# circuit_diagram.net
KiCad netlist of a schematic drawn in EAGLE
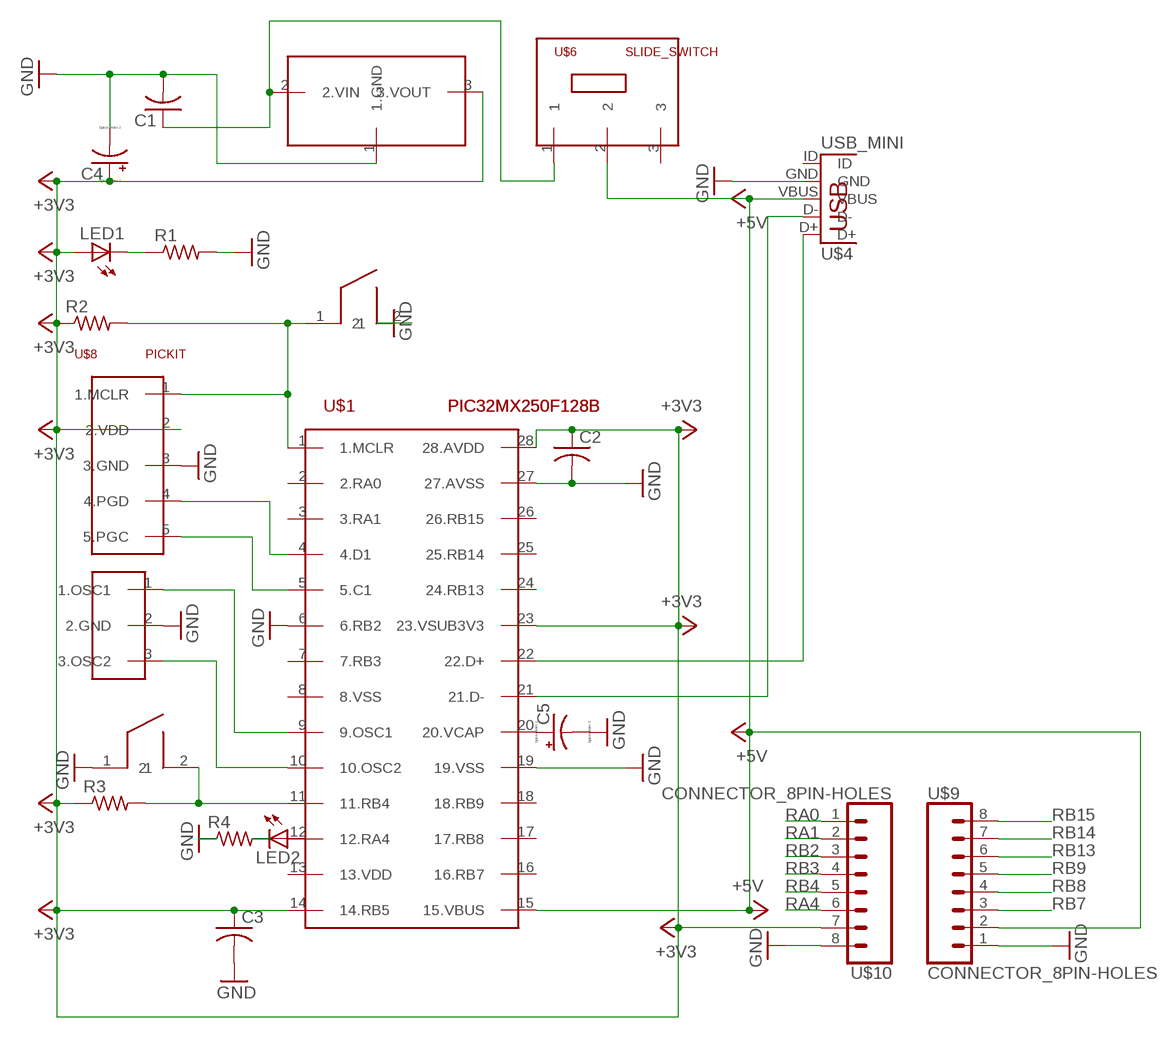
[diagram p0: schematic, sheet 1]

(export (version "E")
  (design (tool "Eeschema 10.0.6"))
  (components
    (comp (ref "C1")
      (value "C-US025-024X044")
      (footprint "eagle-import:C025-024X044")
      (libsource (lib "eagle-import") (part "C-US025-024X044"))
    )
    (comp (ref "C2")
      (value "C-US025-024X044")
      (footprint "eagle-import:C025-024X044")
      (libsource (lib "eagle-import") (part "C-US025-024X044"))
    )
    (comp (ref "C3")
      (value "C-US025-024X044")
      (footprint "eagle-import:C025-024X044")
      (libsource (lib "eagle-import") (part "C-US025-024X044"))
    )
    (comp (ref "C4")
      (value "CPOL-USCT3216")
      (footprint "eagle-import:CT3216")
      (libsource (lib "eagle-import") (part "CPOL-USCT3216"))
    )
    (comp (ref "C5")
      (value "CPOL-USCT3216")
      (footprint "eagle-import:CT3216")
      (libsource (lib "eagle-import") (part "CPOL-USCT3216"))
    )
    (comp (ref "LED1")
      (value "LED3MM")
      (footprint "eagle-import:LED3MM")
      (libsource (lib "eagle-import") (part "LED3MM"))
    )
    (comp (ref "LED2")
      (value "LED3MM")
      (footprint "eagle-import:LED3MM")
      (libsource (lib "eagle-import") (part "LED3MM"))
    )
    (comp (ref "R1")
      (value "R-US_0207/10")
      (footprint "eagle-import:0207_10")
      (libsource (lib "eagle-import") (part "R-US_0207/10"))
    )
    (comp (ref "R2")
      (value "R-US_0207/10")
      (footprint "eagle-import:0207_10")
      (libsource (lib "eagle-import") (part "R-US_0207/10"))
    )
    (comp (ref "R3")
      (value "R-US_0207/10")
      (footprint "eagle-import:0207_10")
      (libsource (lib "eagle-import") (part "R-US_0207/10"))
    )
    (comp (ref "R4")
      (value "R-US_0207/10")
      (footprint "eagle-import:0207_10")
      (libsource (lib "eagle-import") (part "R-US_0207/10"))
    )
    (comp (ref "U$1")
      (value "PIC32MX250F128B")
      (footprint "eagle-import:DIL28-3")
      (libsource (lib "eagle-import") (part "PIC32MX250F128B"))
    )
    (comp (ref "U$2")
      (value "PUSH_BUTTON_SPST-NO")
      (footprint "eagle-import:1X03")
      (libsource (lib "eagle-import") (part "PUSH_BUTTON_SPST-NO"))
    )
    (comp (ref "U$3")
      (value "PUSH_BUTTON_SPST-NO")
      (footprint "eagle-import:1X03")
      (libsource (lib "eagle-import") (part "PUSH_BUTTON_SPST-NO"))
    )
    (comp (ref "U$4")
      (value "USB_MINI")
      (footprint "eagle-import:USB-MB-H")
      (libsource (lib "eagle-import") (part "USB_MINI"))
    )
    (comp (ref "U$5")
      (value "MCP1072")
      (footprint "eagle-import:TO92")
      (libsource (lib "eagle-import") (part "MCP1072"))
    )
    (comp (ref "U$6")
      (value "SLIDE_SWITCH")
      (footprint "eagle-import:SLIDE_SW")
      (libsource (lib "eagle-import") (part "SLIDE_SWITCH"))
    )
    (comp (ref "U$7")
      (value "OSC")
      (footprint "eagle-import:1X03")
      (libsource (lib "eagle-import") (part "OSC"))
    )
    (comp (ref "U$8")
      (value "PICKIT")
      (footprint "eagle-import:1X05")
      (libsource (lib "eagle-import") (part "PICKIT"))
    )
    (comp (ref "U$9")
      (value "CONNECTOR_8PIN-HOLES")
      (footprint "eagle-import:1X08")
      (libsource (lib "eagle-import") (part "CONNECTOR_8PIN-HOLES"))
    )
    (comp (ref "U$10")
      (value "CONNECTOR_8PIN-HOLES")
      (footprint "eagle-import:1X08")
      (libsource (lib "eagle-import") (part "CONNECTOR_8PIN-HOLES"))
    )
  )
  (nets
    (net (code "1") (name "+3V3") (class "Default")
      (node (ref "C2") (pin "1") (pinfunction "1_1") (pintype "passive"))
      (node (ref "C3") (pin "1") (pinfunction "1_1") (pintype "passive"))
      (node (ref "C4") (pin "-") (pinfunction "+_-") (pintype "passive"))
      (node (ref "LED1") (pin "A") (pinfunction "A_A") (pintype "passive"))
      (node (ref "R2") (pin "1") (pinfunction "1_1") (pintype "passive"))
      (node (ref "R3") (pin "1") (pinfunction "1_1") (pintype "passive"))
      (node (ref "U$1") (pin "14") (pinfunction "14.RB5_14") (pintype "bidirectional"))
      (node (ref "U$1") (pin "23") (pinfunction "23.VSUB3V3_23") (pintype "bidirectional"))
      (node (ref "U$1") (pin "28") (pinfunction "28.AVDD_28") (pintype "bidirectional"))
      (node (ref "U$10") (pin "7") (pinfunction "7_7") (pintype "passive"))
      (node (ref "U$5") (pin "3") (pinfunction "3.VOUT_3") (pintype "bidirectional"))
      (node (ref "U$8") (pin "2") (pinfunction "2.VDD_2") (pintype "bidirectional"))
    )
    (net (code "2") (name "+5V") (class "Default")
      (node (ref "U$1") (pin "15") (pinfunction "15.VBUS_15") (pintype "bidirectional"))
      (node (ref "U$4") (pin "VBUS") (pinfunction "VBUS_VBUS") (pintype "bidirectional"))
      (node (ref "U$6") (pin "2") (pinfunction "2_2") (pintype "bidirectional"))
      (node (ref "U$9") (pin "2") (pinfunction "2_2") (pintype "passive"))
    )
    (net (code "3") (name "/RA0") (class "Default")
      (node (ref "U$10") (pin "1") (pinfunction "1_1") (pintype "passive"))
    )
    (net (code "4") (name "/RA1") (class "Default")
      (node (ref "U$10") (pin "2") (pinfunction "2_2") (pintype "passive"))
    )
    (net (code "5") (name "/RA4") (class "Default")
      (node (ref "U$10") (pin "6") (pinfunction "6_6") (pintype "passive"))
    )
    (net (code "6") (name "/RB2") (class "Default")
      (node (ref "U$10") (pin "3") (pinfunction "3_3") (pintype "passive"))
    )
    (net (code "7") (name "/RB3") (class "Default")
      (node (ref "U$10") (pin "4") (pinfunction "4_4") (pintype "passive"))
    )
    (net (code "8") (name "/RB4") (class "Default")
      (node (ref "U$10") (pin "5") (pinfunction "5_5") (pintype "passive"))
    )
    (net (code "9") (name "/RB7") (class "Default")
      (node (ref "U$9") (pin "3") (pinfunction "3_3") (pintype "passive"))
    )
    (net (code "10") (name "/RB8") (class "Default")
      (node (ref "U$9") (pin "4") (pinfunction "4_4") (pintype "passive"))
    )
    (net (code "11") (name "/RB9") (class "Default")
      (node (ref "U$9") (pin "5") (pinfunction "5_5") (pintype "passive"))
    )
    (net (code "12") (name "/RB13") (class "Default")
      (node (ref "U$9") (pin "6") (pinfunction "6_6") (pintype "passive"))
    )
    (net (code "13") (name "/RB14") (class "Default")
      (node (ref "U$9") (pin "7") (pinfunction "7_7") (pintype "passive"))
    )
    (net (code "14") (name "/RB15") (class "Default")
      (node (ref "U$9") (pin "8") (pinfunction "8_8") (pintype "passive"))
    )
    (net (code "15") (name "GND") (class "Default")
      (node (ref "C1") (pin "2") (pinfunction "2_2") (pintype "passive"))
      (node (ref "C2") (pin "2") (pinfunction "2_2") (pintype "passive"))
      (node (ref "C3") (pin "2") (pinfunction "2_2") (pintype "passive"))
      (node (ref "C4") (pin "+") (pinfunction "-_+") (pintype "passive"))
      (node (ref "C5") (pin "+") (pinfunction "-_+") (pintype "passive"))
      (node (ref "R1") (pin "2") (pinfunction "2_2") (pintype "passive"))
      (node (ref "R4") (pin "1") (pinfunction "1_1") (pintype "passive"))
      (node (ref "U$1") (pin "19") (pinfunction "19.VSS_19") (pintype "bidirectional"))
      (node (ref "U$1") (pin "27") (pinfunction "27.AVSS_27") (pintype "bidirectional"))
      (node (ref "U$1") (pin "6") (pinfunction "6.RB2_6") (pintype "bidirectional"))
      (node (ref "U$10") (pin "8") (pinfunction "8_8") (pintype "passive"))
      (node (ref "U$2") (pin "2") (pinfunction "2_2") (pintype "bidirectional"))
      (node (ref "U$3") (pin "1") (pinfunction "1_1") (pintype "bidirectional"))
      (node (ref "U$4") (pin "GND") (pinfunction "GND_GND") (pintype "bidirectional"))
      (node (ref "U$5") (pin "1") (pinfunction "1.GND_1") (pintype "bidirectional"))
      (node (ref "U$7") (pin "2") (pinfunction "2.GND_2") (pintype "bidirectional"))
      (node (ref "U$8") (pin "3") (pinfunction "3.GND_3") (pintype "bidirectional"))
      (node (ref "U$9") (pin "1") (pinfunction "1_1") (pintype "passive"))
    )
    (net (code "16") (name "Net-(C5-+)") (class "Default")
      (node (ref "C5") (pin "-") (pinfunction "+_-") (pintype "passive"))
      (node (ref "U$1") (pin "20") (pinfunction "20.VCAP_20") (pintype "bidirectional"))
    )
    (net (code "17") (name "Net-(LED1-C)") (class "Default")
      (node (ref "LED1") (pin "K") (pinfunction "C_K") (pintype "passive"))
      (node (ref "R1") (pin "1") (pinfunction "1_1") (pintype "passive"))
    )
    (net (code "18") (name "Net-(LED2-C)") (class "Default")
      (node (ref "LED2") (pin "K") (pinfunction "C_K") (pintype "passive"))
      (node (ref "R4") (pin "2") (pinfunction "2_2") (pintype "passive"))
    )
    (net (code "19") (name "Net-(U$1-1.MCLR)") (class "Default")
      (node (ref "R2") (pin "2") (pinfunction "2_2") (pintype "passive"))
      (node (ref "U$1") (pin "1") (pinfunction "1.MCLR_1") (pintype "bidirectional"))
      (node (ref "U$2") (pin "1") (pinfunction "1_1") (pintype "bidirectional"))
      (node (ref "U$8") (pin "1") (pinfunction "1.MCLR_1") (pintype "bidirectional"))
    )
    (net (code "20") (name "Net-(U$1-4.D1)") (class "Default")
      (node (ref "U$1") (pin "4") (pinfunction "4.D1_4") (pintype "bidirectional"))
      (node (ref "U$8") (pin "4") (pinfunction "4.PGD_4") (pintype "bidirectional"))
    )
    (net (code "21") (name "Net-(U$1-5.C1)") (class "Default")
      (node (ref "U$1") (pin "5") (pinfunction "5.C1_5") (pintype "bidirectional"))
      (node (ref "U$8") (pin "5") (pinfunction "5.PGC_5") (pintype "bidirectional"))
    )
    (net (code "22") (name "Net-(U$1-9.OSC1)") (class "Default")
      (node (ref "U$1") (pin "9") (pinfunction "9.OSC1_9") (pintype "bidirectional"))
      (node (ref "U$7") (pin "1") (pinfunction "1.OSC1_1") (pintype "bidirectional"))
    )
    (net (code "23") (name "Net-(U$1-10.OSC2)") (class "Default")
      (node (ref "U$1") (pin "10") (pinfunction "10.OSC2_10") (pintype "bidirectional"))
      (node (ref "U$7") (pin "3") (pinfunction "3.OSC2_3") (pintype "bidirectional"))
    )
    (net (code "24") (name "Net-(U$1-11.RB4)") (class "Default")
      (node (ref "R3") (pin "2") (pinfunction "2_2") (pintype "passive"))
      (node (ref "U$1") (pin "11") (pinfunction "11.RB4_11") (pintype "bidirectional"))
      (node (ref "U$3") (pin "2") (pinfunction "2_2") (pintype "bidirectional"))
    )
    (net (code "25") (name "Net-(U$1-21.D-)") (class "Default")
      (node (ref "U$1") (pin "21") (pinfunction "21.D-_21") (pintype "bidirectional"))
      (node (ref "U$4") (pin "D-") (pinfunction "D-_D-") (pintype "bidirectional"))
    )
    (net (code "26") (name "Net-(U$1-22.D+)") (class "Default")
      (node (ref "U$1") (pin "22") (pinfunction "22.D+_22") (pintype "bidirectional"))
      (node (ref "U$4") (pin "D+") (pinfunction "D+_D+") (pintype "bidirectional"))
    )
    (net (code "27") (name "Net-(U$5-2.VIN)") (class "Default")
      (node (ref "C1") (pin "1") (pinfunction "1_1") (pintype "passive"))
      (node (ref "U$5") (pin "2") (pinfunction "2.VIN_2") (pintype "bidirectional"))
      (node (ref "U$6") (pin "1") (pinfunction "1_1") (pintype "bidirectional"))
    )
    (net (code "28") (name "unconnected-(LED2-PadA)") (class "Default")
      (node (ref "LED2") (pin "A") (pinfunction "A_A") (pintype "passive"))
    )
    (net (code "29") (name "unconnected-(U$1-2.RA0-Pad2)") (class "Default")
      (node (ref "U$1") (pin "2") (pinfunction "2.RA0_2") (pintype "bidirectional"))
    )
    (net (code "30") (name "unconnected-(U$1-3.RA1-Pad3)") (class "Default")
      (node (ref "U$1") (pin "3") (pinfunction "3.RA1_3") (pintype "bidirectional"))
    )
    (net (code "31") (name "unconnected-(U$1-7.RB3-Pad7)") (class "Default")
      (node (ref "U$1") (pin "7") (pinfunction "7.RB3_7") (pintype "bidirectional"))
    )
    (net (code "32") (name "unconnected-(U$1-8.VSS-Pad8)") (class "Default")
      (node (ref "U$1") (pin "8") (pinfunction "8.VSS_8") (pintype "bidirectional"))
    )
    (net (code "33") (name "unconnected-(U$1-12.RA4-Pad12)") (class "Default")
      (node (ref "U$1") (pin "12") (pinfunction "12.RA4_12") (pintype "bidirectional"))
    )
    (net (code "34") (name "unconnected-(U$1-13.VDD-Pad13)") (class "Default")
      (node (ref "U$1") (pin "13") (pinfunction "13.VDD_13") (pintype "bidirectional"))
    )
    (net (code "35") (name "unconnected-(U$1-16.RB7-Pad16)") (class "Default")
      (node (ref "U$1") (pin "16") (pinfunction "16.RB7_16") (pintype "bidirectional"))
    )
    (net (code "36") (name "unconnected-(U$1-17.RB8-Pad17)") (class "Default")
      (node (ref "U$1") (pin "17") (pinfunction "17.RB8_17") (pintype "bidirectional"))
    )
    (net (code "37") (name "unconnected-(U$1-18.RB9-Pad18)") (class "Default")
      (node (ref "U$1") (pin "18") (pinfunction "18.RB9_18") (pintype "bidirectional"))
    )
    (net (code "38") (name "unconnected-(U$1-24.RB13-Pad24)") (class "Default")
      (node (ref "U$1") (pin "24") (pinfunction "24.RB13_24") (pintype "bidirectional"))
    )
    (net (code "39") (name "unconnected-(U$1-25.RB14-Pad25)") (class "Default")
      (node (ref "U$1") (pin "25") (pinfunction "25.RB14_25") (pintype "bidirectional"))
    )
    (net (code "40") (name "unconnected-(U$1-26.RB15-Pad26)") (class "Default")
      (node (ref "U$1") (pin "26") (pinfunction "26.RB15_26") (pintype "bidirectional"))
    )
    (net (code "41") (name "unconnected-(U$4-PadID)") (class "Default")
      (node (ref "U$4") (pin "ID") (pinfunction "ID_ID") (pintype "bidirectional"))
    )
    (net (code "42") (name "unconnected-(U$6-Pad3)") (class "Default")
      (node (ref "U$6") (pin "3") (pinfunction "3_3") (pintype "bidirectional"))
    )
  )
)
